# main.net
KiCad netlist of a schematic drawn in EAGLE
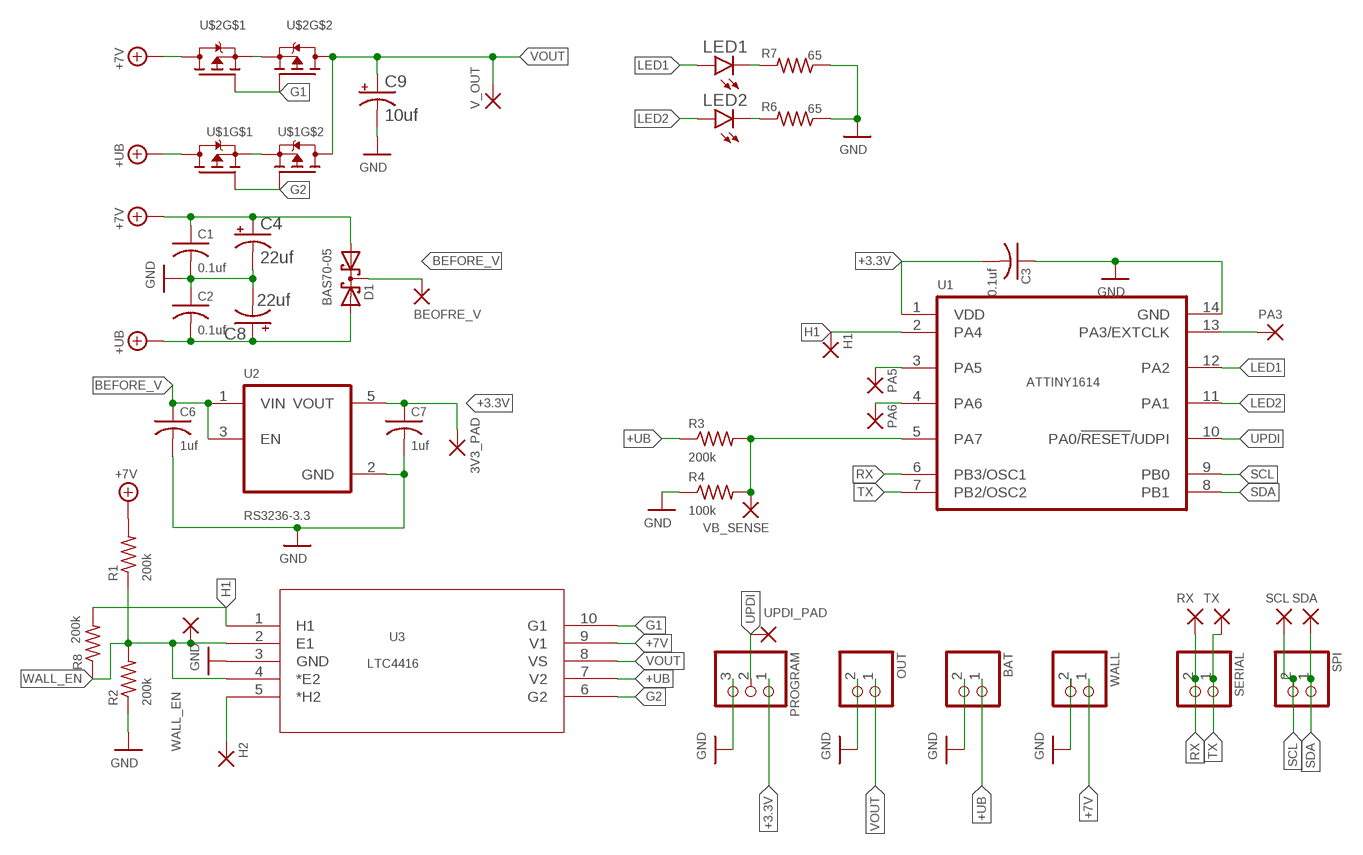
[diagram p0: schematic, sheet 1]

(export (version "E")
  (design (tool "Eeschema 10.0.6"))
  (components
    (comp (ref "3V3_PAD")
      (value "SMD2")
      (footprint "eagle-import:SMD1,27-2,54")
      (libsource (lib "eagle-import") (part "SMD2"))
    )
    (comp (ref "BAT")
      (value "PINHD-1X2")
      (footprint "eagle-import:1X02")
      (libsource (lib "eagle-import") (part "PINHD-1X2"))
    )
    (comp (ref "BEOFRE_V")
      (value "SMD2")
      (footprint "eagle-import:SMD1,27-2,54")
      (libsource (lib "eagle-import") (part "SMD2"))
    )
    (comp (ref "C1")
      (value "0.1uf")
      (footprint "eagle-import:C0805")
      (libsource (lib "eagle-import") (part "C-USC0805"))
    )
    (comp (ref "C2")
      (value "0.1uf")
      (footprint "eagle-import:C0805")
      (libsource (lib "eagle-import") (part "C-USC0805"))
    )
    (comp (ref "C3")
      (value "0.1uf")
      (footprint "eagle-import:C0805")
      (libsource (lib "eagle-import") (part "C-USC0805"))
    )
    (comp (ref "C4")
      (value "22uf")
      (footprint "eagle-import:153CLV-0405")
      (libsource (lib "eagle-import") (part "CPOL-US153CLV-0405"))
    )
    (comp (ref "C6")
      (value "1uf")
      (footprint "eagle-import:C1210")
      (libsource (lib "eagle-import") (part "C-USC1210"))
    )
    (comp (ref "C7")
      (value "1uf")
      (footprint "eagle-import:C1210")
      (libsource (lib "eagle-import") (part "C-USC1210"))
    )
    (comp (ref "C8")
      (value "22uf")
      (footprint "eagle-import:153CLV-0405")
      (libsource (lib "eagle-import") (part "CPOL-US153CLV-0405"))
    )
    (comp (ref "C9")
      (value "10uf")
      (footprint "eagle-import:153CLV-0405")
      (libsource (lib "eagle-import") (part "CPOL-US153CLV-0405"))
    )
    (comp (ref "D1")
      (value "BAS70-05")
      (footprint "eagle-import:SOT23")
      (fields (field (name "MF") "NXP Semiconductors"))
      (libsource (lib "eagle-import") (part "BAS70-05"))
    )
    (comp (ref "H1")
      (value "SMD2")
      (footprint "eagle-import:SMD1,27-2,54")
      (libsource (lib "eagle-import") (part "SMD2"))
    )
    (comp (ref "H2")
      (value "SMD2")
      (footprint "eagle-import:SMD1,27-2,54")
      (libsource (lib "eagle-import") (part "SMD2"))
    )
    (comp (ref "LED1")
      (value "LEDCHIP-LED0805")
      (footprint "eagle-import:CHIP-LED0805")
      (libsource (lib "eagle-import") (part "LEDCHIP-LED0805"))
    )
    (comp (ref "LED2")
      (value "LEDCHIP-LED0805")
      (footprint "eagle-import:CHIP-LED0805")
      (libsource (lib "eagle-import") (part "LEDCHIP-LED0805"))
    )
    (comp (ref "OUT")
      (value "PINHD-1X2")
      (footprint "eagle-import:1X02")
      (libsource (lib "eagle-import") (part "PINHD-1X2"))
    )
    (comp (ref "PA3")
      (value "SMD2")
      (footprint "eagle-import:SMD1,27-2,54")
      (libsource (lib "eagle-import") (part "SMD2"))
    )
    (comp (ref "PA5")
      (value "SMD2")
      (footprint "eagle-import:SMD1,27-2,54")
      (libsource (lib "eagle-import") (part "SMD2"))
    )
    (comp (ref "PA6")
      (value "SMD2")
      (footprint "eagle-import:SMD1,27-2,54")
      (libsource (lib "eagle-import") (part "SMD2"))
    )
    (comp (ref "PROGRAM")
      (value "PINHD-1X3")
      (footprint "eagle-import:1X03")
      (libsource (lib "eagle-import") (part "PINHD-1X3"))
    )
    (comp (ref "R1")
      (value "200k")
      (footprint "eagle-import:R0805")
      (libsource (lib "eagle-import") (part "R-US_R0805"))
    )
    (comp (ref "R2")
      (value "200k")
      (footprint "eagle-import:R0805")
      (libsource (lib "eagle-import") (part "R-US_R0805"))
    )
    (comp (ref "R3")
      (value "200k")
      (footprint "eagle-import:R0805")
      (libsource (lib "eagle-import") (part "R-US_R0805"))
    )
    (comp (ref "R4")
      (value "100k")
      (footprint "eagle-import:R0805")
      (libsource (lib "eagle-import") (part "R-US_R0805"))
    )
    (comp (ref "R6")
      (value "65")
      (footprint "eagle-import:R0805")
      (libsource (lib "eagle-import") (part "R-US_R0805"))
    )
    (comp (ref "R7")
      (value "65")
      (footprint "eagle-import:R0805")
      (libsource (lib "eagle-import") (part "R-US_R0805"))
    )
    (comp (ref "R8")
      (value "200k")
      (footprint "eagle-import:R0805")
      (libsource (lib "eagle-import") (part "R-US_R0805"))
    )
    (comp (ref "RX")
      (value "SMD2")
      (footprint "eagle-import:SMD1,27-2,54")
      (libsource (lib "eagle-import") (part "SMD2"))
    )
    (comp (ref "SCL")
      (value "SMD2")
      (footprint "eagle-import:SMD1,27-2,54")
      (libsource (lib "eagle-import") (part "SMD2"))
    )
    (comp (ref "SDA")
      (value "SMD2")
      (footprint "eagle-import:SMD1,27-2,54")
      (libsource (lib "eagle-import") (part "SMD2"))
    )
    (comp (ref "SERIAL")
      (value "PINHD-1X2")
      (footprint "eagle-import:1X02")
      (libsource (lib "eagle-import") (part "PINHD-1X2"))
    )
    (comp (ref "SPI")
      (value "PINHD-1X2")
      (footprint "eagle-import:1X02")
      (libsource (lib "eagle-import") (part "PINHD-1X2"))
    )
    (comp (ref "TX")
      (value "SMD2")
      (footprint "eagle-import:SMD1,27-2,54")
      (libsource (lib "eagle-import") (part "SMD2"))
    )
    (comp (ref "U$1")
      (value "IRF7314PBF")
      (footprint "eagle-import:SO-8")
      (fields (field (name "MF") "Infineon"))
      (libsource (lib "eagle-import") (part "IRF7314PBF"))
    )
    (comp (ref "U$2")
      (value "IRF7314PBF")
      (footprint "eagle-import:SO-8")
      (fields (field (name "MF") "Infineon"))
      (libsource (lib "eagle-import") (part "IRF7314PBF"))
    )
    (comp (ref "U1")
      (value "ATTINY1614")
      (footprint "eagle-import:SOIC127P600X175-14N")
      (fields (field (name "MF") "Microchip") (field (name "MP") "ATTINY1614-SSNR"))
      (libsource (lib "eagle-import") (part "ATTINY1614-SSNR"))
    )
    (comp (ref "U2")
      (value "RS3236-3.3")
      (footprint "eagle-import:SOT95P285X140-5N")
      (fields (field (name "MF") "Diodes Inc.") (field (name "MP") "AP2112K-3.3TRG1"))
      (libsource (lib "eagle-import") (part "AP2112K-3.3TRG1"))
    )
    (comp (ref "U3")
      (value "LTC4416")
      (footprint "eagle-import:MSOP-10_MS")
      (fields (field (name "MF") "Analog Devices") (field (name "MP") "LTC4416IMS#PBF"))
      (libsource (lib "eagle-import") (part "LTC4416IMS#PBF"))
    )
    (comp (ref "UPDI_PAD")
      (value "SMD2")
      (footprint "eagle-import:SMD1,27-2,54")
      (libsource (lib "eagle-import") (part "SMD2"))
    )
    (comp (ref "VB_SENSE")
      (value "SMD2")
      (footprint "eagle-import:SMD1,27-2,54")
      (libsource (lib "eagle-import") (part "SMD2"))
    )
    (comp (ref "V_OUT")
      (value "SMD2")
      (footprint "eagle-import:SMD1,27-2,54")
      (libsource (lib "eagle-import") (part "SMD2"))
    )
    (comp (ref "WALL")
      (value "PINHD-1X2")
      (footprint "eagle-import:1X02")
      (libsource (lib "eagle-import") (part "PINHD-1X2"))
    )
    (comp (ref "WALL_EN")
      (value "SMD2")
      (footprint "eagle-import:SMD1,27-2,54")
      (libsource (lib "eagle-import") (part "SMD2"))
    )
  )
  (nets
    (net (code "1") (name "+3.3V") (class "Default")
      (node (ref "3V3_PAD") (pin "1") (pinfunction "P_1") (pintype "passive"))
      (node (ref "C3") (pin "2") (pinfunction "2_2") (pintype "passive"))
      (node (ref "C7") (pin "1") (pinfunction "1_1") (pintype "passive"))
      (node (ref "PROGRAM") (pin "1") (pinfunction "1_1") (pintype "passive"))
      (node (ref "U1") (pin "1") (pinfunction "VDD_1") (pintype "power_in"))
      (node (ref "U2") (pin "5") (pinfunction "VOUT_5") (pintype "power_in"))
    )
    (net (code "2") (name "+7V") (class "Default")
      (node (ref "C1") (pin "1") (pinfunction "1_1") (pintype "passive"))
      (node (ref "C4") (pin "+") (pinfunction "+_+") (pintype "passive"))
      (node (ref "D1") (pin "1") (pinfunction "A1_1") (pintype "passive"))
      (node (ref "R1") (pin "2") (pinfunction "2_2") (pintype "passive"))
      (node (ref "U$2") (pin "7") (pinfunction "D_7") (pintype "passive"))
      (node (ref "U$2") (pin "8") (pinfunction "D_8") (pintype "passive"))
      (node (ref "U3") (pin "9") (pinfunction "V1_9") (pintype "input"))
      (node (ref "WALL") (pin "1") (pinfunction "1_1") (pintype "passive"))
    )
    (net (code "3") (name "+UB") (class "Default")
      (node (ref "BAT") (pin "1") (pinfunction "1_1") (pintype "passive"))
      (node (ref "C2") (pin "2") (pinfunction "2_2") (pintype "passive"))
      (node (ref "C8") (pin "+") (pinfunction "+_+") (pintype "passive"))
      (node (ref "D1") (pin "2") (pinfunction "A2_2") (pintype "passive"))
      (node (ref "R3") (pin "1") (pinfunction "1_1") (pintype "passive"))
      (node (ref "U$1") (pin "7") (pinfunction "D_7") (pintype "passive"))
      (node (ref "U$1") (pin "8") (pinfunction "D_8") (pintype "passive"))
      (node (ref "U3") (pin "7") (pinfunction "V2_7") (pintype "input"))
    )
    (net (code "4") (name "BEFORE_V") (class "Default")
      (node (ref "BEOFRE_V") (pin "1") (pinfunction "P_1") (pintype "passive"))
      (node (ref "C6") (pin "1") (pinfunction "1_1") (pintype "passive"))
      (node (ref "D1") (pin "3") (pinfunction "K1K2_3") (pintype "passive"))
      (node (ref "U2") (pin "1") (pinfunction "VIN_1") (pintype "power_in"))
      (node (ref "U2") (pin "3") (pinfunction "EN_3") (pintype "input"))
    )
    (net (code "5") (name "G1") (class "Default")
      (node (ref "U$2") (pin "2") (pinfunction "G_2") (pintype "passive"))
      (node (ref "U$2") (pin "4") (pinfunction "G_4") (pintype "passive"))
      (node (ref "U3") (pin "10") (pinfunction "G1_10") (pintype "passive"))
    )
    (net (code "6") (name "G2") (class "Default")
      (node (ref "U$1") (pin "2") (pinfunction "G_2") (pintype "passive"))
      (node (ref "U$1") (pin "4") (pinfunction "G_4") (pintype "passive"))
      (node (ref "U3") (pin "6") (pinfunction "G2_6") (pintype "passive"))
    )
    (net (code "7") (name "GND") (class "Default")
      (node (ref "BAT") (pin "2") (pinfunction "2_2") (pintype "passive"))
      (node (ref "C1") (pin "2") (pinfunction "2_2") (pintype "passive"))
      (node (ref "C2") (pin "1") (pinfunction "1_1") (pintype "passive"))
      (node (ref "C3") (pin "1") (pinfunction "1_1") (pintype "passive"))
      (node (ref "C4") (pin "-") (pinfunction "-_-") (pintype "passive"))
      (node (ref "C6") (pin "2") (pinfunction "2_2") (pintype "passive"))
      (node (ref "C7") (pin "2") (pinfunction "2_2") (pintype "passive"))
      (node (ref "C8") (pin "-") (pinfunction "-_-") (pintype "passive"))
      (node (ref "C9") (pin "-") (pinfunction "-_-") (pintype "passive"))
      (node (ref "OUT") (pin "2") (pinfunction "2_2") (pintype "passive"))
      (node (ref "PROGRAM") (pin "3") (pinfunction "3_3") (pintype "passive"))
      (node (ref "R2") (pin "1") (pinfunction "1_1") (pintype "passive"))
      (node (ref "R4") (pin "1") (pinfunction "1_1") (pintype "passive"))
      (node (ref "R6") (pin "1") (pinfunction "1_1") (pintype "passive"))
      (node (ref "R7") (pin "1") (pinfunction "1_1") (pintype "passive"))
      (node (ref "U1") (pin "14") (pinfunction "GND_14") (pintype "power_in"))
      (node (ref "U2") (pin "2") (pinfunction "GND_2") (pintype "power_in"))
      (node (ref "U3") (pin "3") (pinfunction "GND_3") (pintype "power_in"))
      (node (ref "WALL") (pin "2") (pinfunction "2_2") (pintype "passive"))
    )
    (net (code "8") (name "H1") (class "Default")
      (node (ref "H1") (pin "1") (pinfunction "P_1") (pintype "passive"))
      (node (ref "R8") (pin "2") (pinfunction "2_2") (pintype "passive"))
      (node (ref "U1") (pin "2") (pinfunction "PA4_2") (pintype "bidirectional"))
      (node (ref "U3") (pin "1") (pinfunction "H1_1") (pintype "output"))
    )
    (net (code "9") (name "LED1") (class "Default")
      (node (ref "LED1") (pin "A") (pinfunction "A_A") (pintype "passive"))
      (node (ref "U1") (pin "12") (pinfunction "PA2_12") (pintype "bidirectional"))
    )
    (net (code "10") (name "LED2") (class "Default")
      (node (ref "LED2") (pin "A") (pinfunction "A_A") (pintype "passive"))
      (node (ref "U1") (pin "11") (pinfunction "PA1_11") (pintype "bidirectional"))
    )
    (net (code "11") (name "Net-(H2-P)") (class "Default")
      (node (ref "H2") (pin "1") (pinfunction "P_1") (pintype "passive"))
      (node (ref "U3") (pin "5") (pinfunction "*H2_5") (pintype "input"))
    )
    (net (code "12") (name "Net-(LED1-PadC)") (class "Default")
      (node (ref "LED1") (pin "C") (pinfunction "C_C") (pintype "passive"))
      (node (ref "R7") (pin "2") (pinfunction "2_2") (pintype "passive"))
    )
    (net (code "13") (name "Net-(LED2-PadC)") (class "Default")
      (node (ref "LED2") (pin "C") (pinfunction "C_C") (pintype "passive"))
      (node (ref "R6") (pin "2") (pinfunction "2_2") (pintype "passive"))
    )
    (net (code "14") (name "Net-(PA3-P)") (class "Default")
      (node (ref "PA3") (pin "1") (pinfunction "P_1") (pintype "passive"))
      (node (ref "U1") (pin "13") (pinfunction "PA3/EXTCLK_13") (pintype "bidirectional"))
    )
    (net (code "15") (name "Net-(PA5-P)") (class "Default")
      (node (ref "PA5") (pin "1") (pinfunction "P_1") (pintype "passive"))
      (node (ref "U1") (pin "3") (pinfunction "PA5_3") (pintype "bidirectional"))
    )
    (net (code "16") (name "Net-(PA6-P)") (class "Default")
      (node (ref "PA6") (pin "1") (pinfunction "P_1") (pintype "passive"))
      (node (ref "U1") (pin "4") (pinfunction "PA6_4") (pintype "bidirectional"))
    )
    (net (code "17") (name "Net-(U$1A-S)") (class "Default")
      (node (ref "U$1") (pin "1") (pinfunction "S_1") (pintype "passive"))
      (node (ref "U$1") (pin "3") (pinfunction "S_3") (pintype "passive"))
    )
    (net (code "18") (name "Net-(U$2A-S)") (class "Default")
      (node (ref "U$2") (pin "1") (pinfunction "S_1") (pintype "passive"))
      (node (ref "U$2") (pin "3") (pinfunction "S_3") (pintype "passive"))
    )
    (net (code "19") (name "Net-(U1-PA7)") (class "Default")
      (node (ref "R3") (pin "2") (pinfunction "2_2") (pintype "passive"))
      (node (ref "R4") (pin "2") (pinfunction "2_2") (pintype "passive"))
      (node (ref "U1") (pin "5") (pinfunction "PA7_5") (pintype "bidirectional"))
      (node (ref "VB_SENSE") (pin "1") (pinfunction "P_1") (pintype "passive"))
    )
    (net (code "20") (name "RX") (class "Default")
      (node (ref "RX") (pin "1") (pinfunction "P_1") (pintype "passive"))
      (node (ref "SERIAL") (pin "2") (pinfunction "2_2") (pintype "passive"))
      (node (ref "U1") (pin "6") (pinfunction "PB3/OSC1_6") (pintype "bidirectional"))
    )
    (net (code "21") (name "SCL") (class "Default")
      (node (ref "SCL") (pin "1") (pinfunction "P_1") (pintype "passive"))
      (node (ref "SPI") (pin "2") (pinfunction "2_2") (pintype "passive"))
      (node (ref "U1") (pin "9") (pinfunction "PB0_9") (pintype "bidirectional"))
    )
    (net (code "22") (name "SDA") (class "Default")
      (node (ref "SDA") (pin "1") (pinfunction "P_1") (pintype "passive"))
      (node (ref "SPI") (pin "1") (pinfunction "1_1") (pintype "passive"))
      (node (ref "U1") (pin "8") (pinfunction "PB1_8") (pintype "bidirectional"))
    )
    (net (code "23") (name "TX") (class "Default")
      (node (ref "SERIAL") (pin "1") (pinfunction "1_1") (pintype "passive"))
      (node (ref "TX") (pin "1") (pinfunction "P_1") (pintype "passive"))
      (node (ref "U1") (pin "7") (pinfunction "PB2/OSC2_7") (pintype "bidirectional"))
    )
    (net (code "24") (name "UPDI") (class "Default")
      (node (ref "PROGRAM") (pin "2") (pinfunction "2_2") (pintype "passive"))
      (node (ref "U1") (pin "10") (pinfunction "PA0/~{RESET}/UDPI_10") (pintype "bidirectional"))
      (node (ref "UPDI_PAD") (pin "1") (pinfunction "P_1") (pintype "passive"))
    )
    (net (code "25") (name "VOUT") (class "Default")
      (node (ref "C9") (pin "+") (pinfunction "+_+") (pintype "passive"))
      (node (ref "OUT") (pin "1") (pinfunction "1_1") (pintype "passive"))
      (node (ref "U$1") (pin "5") (pinfunction "D_5") (pintype "passive"))
      (node (ref "U$1") (pin "6") (pinfunction "D_6") (pintype "passive"))
      (node (ref "U$2") (pin "5") (pinfunction "D_5") (pintype "passive"))
      (node (ref "U$2") (pin "6") (pinfunction "D_6") (pintype "passive"))
      (node (ref "U3") (pin "8") (pinfunction "VS_8") (pintype "input"))
      (node (ref "V_OUT") (pin "1") (pinfunction "P_1") (pintype "passive"))
    )
    (net (code "26") (name "WALL_EN") (class "Default")
      (node (ref "R1") (pin "1") (pinfunction "1_1") (pintype "passive"))
      (node (ref "R2") (pin "2") (pinfunction "2_2") (pintype "passive"))
      (node (ref "R8") (pin "1") (pinfunction "1_1") (pintype "passive"))
      (node (ref "U3") (pin "2") (pinfunction "E1_2") (pintype "input"))
      (node (ref "U3") (pin "4") (pinfunction "*E2_4") (pintype "input"))
      (node (ref "WALL_EN") (pin "1") (pinfunction "P_1") (pintype "passive"))
    )
  )
)
